# session_8.net
KiCad netlist of a schematic drawn in EAGLE
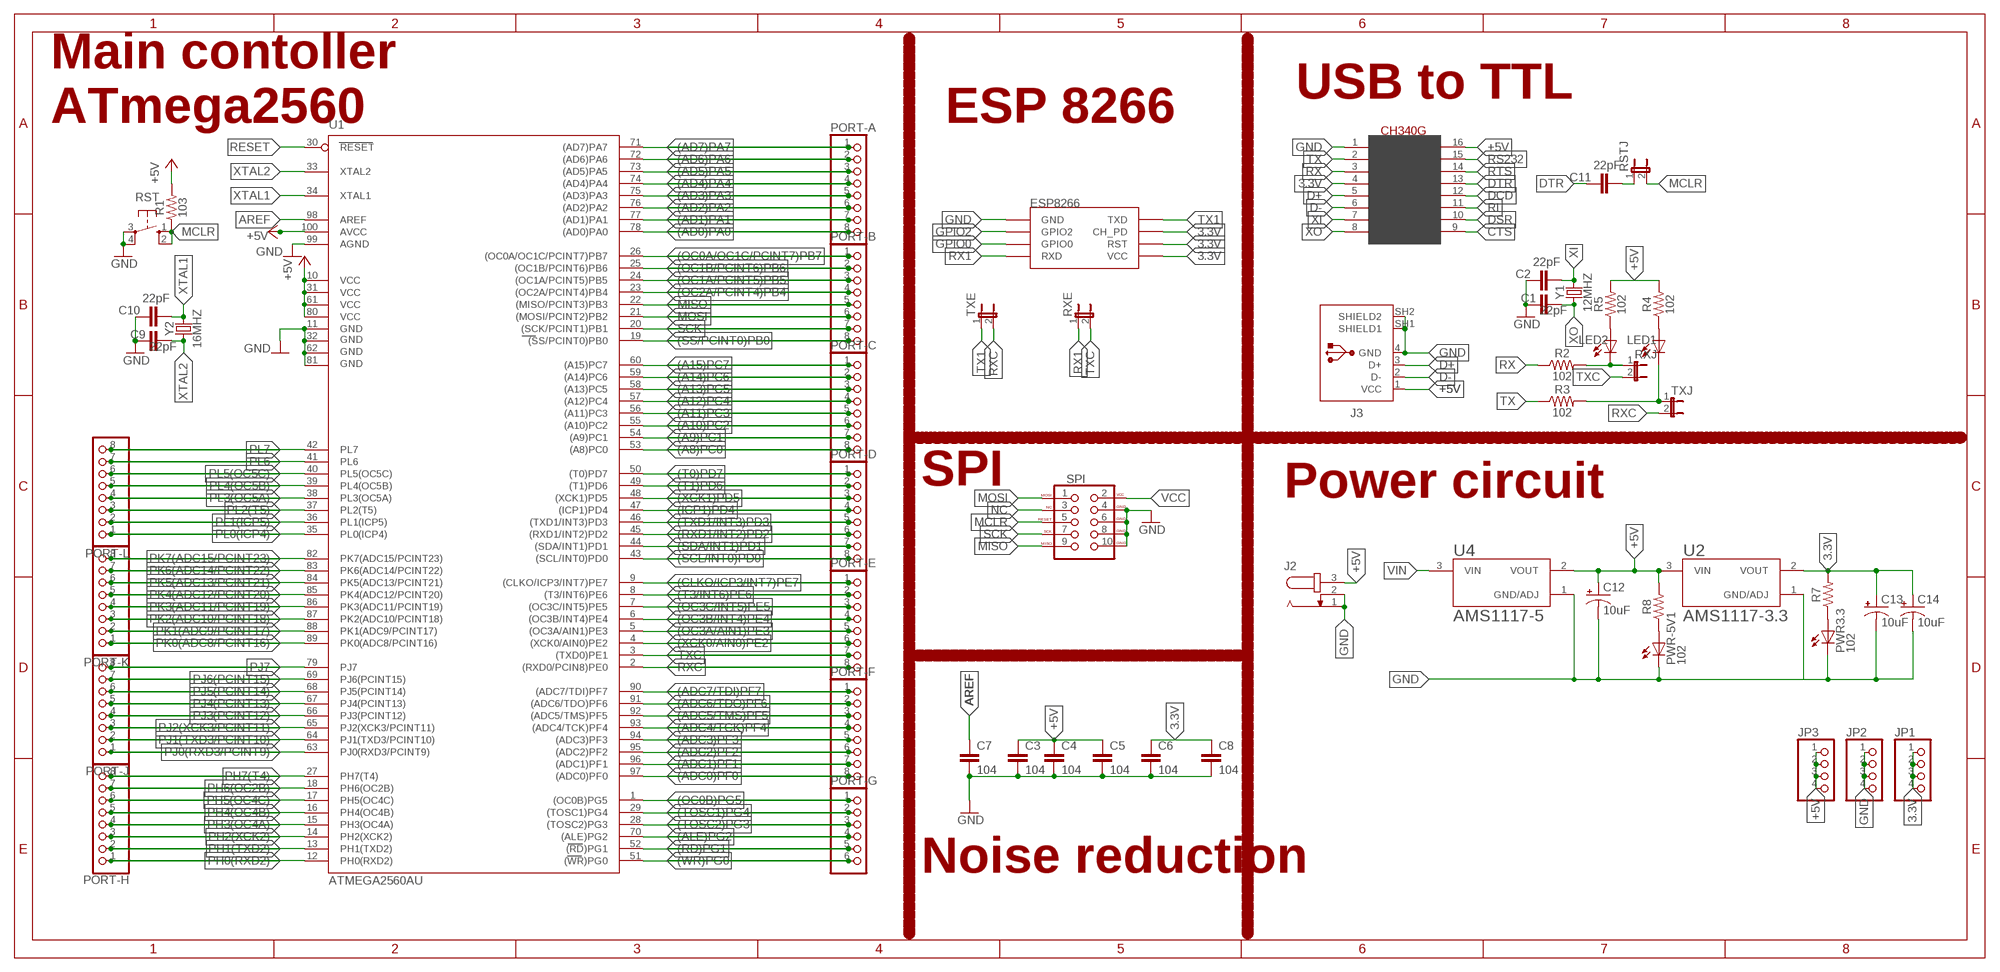
[diagram p0: schematic, sheet 1]

(export (version "E")
  (design (tool "Eeschema 10.0.6"))
  (components
    (comp (ref "C1")
      (value "22pF")
      (footprint "eagle-import:CAP-PTH-2.54")
      (libsource (lib "eagle-import") (part "22PF-PTH-2.54MM-200V-5%"))
    )
    (comp (ref "C2")
      (value "22pF")
      (footprint "eagle-import:CAP-PTH-2.54")
      (libsource (lib "eagle-import") (part "22PF-PTH-2.54MM-200V-5%"))
    )
    (comp (ref "C3")
      (value "104")
      (footprint "eagle-import:CAP-PTH-SMALL-KIT")
      (libsource (lib "eagle-import") (part "0.1UF-KIT-EZ-50V-20%"))
    )
    (comp (ref "C4")
      (value "104")
      (footprint "eagle-import:CAP-PTH-SMALL-KIT")
      (libsource (lib "eagle-import") (part "0.1UF-KIT-EZ-50V-20%"))
    )
    (comp (ref "C5")
      (value "104")
      (footprint "eagle-import:CAP-PTH-SMALL-KIT")
      (libsource (lib "eagle-import") (part "0.1UF-KIT-EZ-50V-20%"))
    )
    (comp (ref "C6")
      (value "104")
      (footprint "eagle-import:CAP-PTH-SMALL-KIT")
      (libsource (lib "eagle-import") (part "0.1UF-KIT-EZ-50V-20%"))
    )
    (comp (ref "C7")
      (value "104")
      (footprint "eagle-import:CAP-PTH-SMALL-KIT")
      (libsource (lib "eagle-import") (part "0.1UF-KIT-EZ-50V-20%"))
    )
    (comp (ref "C8")
      (value "104")
      (footprint "eagle-import:CAP-PTH-SMALL-KIT")
      (libsource (lib "eagle-import") (part "0.1UF-KIT-EZ-50V-20%"))
    )
    (comp (ref "C9")
      (value "22pF")
      (footprint "eagle-import:CAP-PTH-2.54")
      (libsource (lib "eagle-import") (part "22PF-PTH-2.54MM-200V-5%"))
    )
    (comp (ref "C10")
      (value "22pF")
      (footprint "eagle-import:CAP-PTH-2.54")
      (libsource (lib "eagle-import") (part "22PF-PTH-2.54MM-200V-5%"))
    )
    (comp (ref "C11")
      (value "22pF")
      (footprint "eagle-import:CAP-PTH-2.54")
      (libsource (lib "eagle-import") (part "22PF-PTH-2.54MM-200V-5%"))
    )
    (comp (ref "C12")
      (value "10uF")
      (footprint "eagle-import:CPOL-RADIAL-2.5MM-5MM")
      (libsource (lib "eagle-import") (part "10UF-POLAR-RADIAL-2.5MM-25V-20%"))
    )
    (comp (ref "C13")
      (value "10uF")
      (footprint "eagle-import:CPOL-RADIAL-2.5MM-5MM")
      (libsource (lib "eagle-import") (part "10UF-POLAR-RADIAL-2.5MM-25V-20%"))
    )
    (comp (ref "C14")
      (value "10uF")
      (footprint "eagle-import:CPOL-RADIAL-2.5MM-5MM")
      (libsource (lib "eagle-import") (part "10UF-POLAR-RADIAL-2.5MM-25V-20%"))
    )
    (comp (ref "ESP8266")
      (value "ESP01")
      (footprint "eagle-import:ESP01")
      (libsource (lib "eagle-import") (part "ESP01"))
    )
    (comp (ref "J2")
      (value "JACK-PLUG1")
      (footprint "eagle-import:SPC4078")
      (libsource (lib "eagle-import") (part "JACK-PLUG1"))
    )
    (comp (ref "J3")
      (value "61729-1011")
      (footprint "eagle-import:61729-1011BLF")
      (fields (field (name "MANUFACTURER") "Amphenol ICC (FCI)") (field (name "MPN") "61729-1011BLF"))
      (libsource (lib "eagle-import") (part "61729-1011"))
    )
    (comp (ref "JP1")
      (value "PINHD-1X4")
      (footprint "eagle-import:1X04")
      (libsource (lib "eagle-import") (part "PINHD-1X4"))
    )
    (comp (ref "JP2")
      (value "PINHD-1X4")
      (footprint "eagle-import:1X04")
      (libsource (lib "eagle-import") (part "PINHD-1X4"))
    )
    (comp (ref "JP3")
      (value "PINHD-1X4")
      (footprint "eagle-import:1X04")
      (libsource (lib "eagle-import") (part "PINHD-1X4"))
    )
    (comp (ref "LED1")
      (value "LEDCHIP-LED0805")
      (footprint "eagle-import:CHIP-LED0805")
      (libsource (lib "eagle-import") (part "LEDCHIP-LED0805"))
    )
    (comp (ref "LED2")
      (value "LEDCHIP-LED0805")
      (footprint "eagle-import:CHIP-LED0805")
      (libsource (lib "eagle-import") (part "LEDCHIP-LED0805"))
    )
    (comp (ref "PORT-A")
      (value "PINHD-1X8")
      (footprint "eagle-import:1X08")
      (libsource (lib "eagle-import") (part "PINHD-1X8"))
    )
    (comp (ref "PORT-B")
      (value "PINHD-1X8")
      (footprint "eagle-import:1X08")
      (libsource (lib "eagle-import") (part "PINHD-1X8"))
    )
    (comp (ref "PORT-C")
      (value "PINHD-1X8")
      (footprint "eagle-import:1X08")
      (libsource (lib "eagle-import") (part "PINHD-1X8"))
    )
    (comp (ref "PORT-D")
      (value "PINHD-1X8")
      (footprint "eagle-import:1X08")
      (libsource (lib "eagle-import") (part "PINHD-1X8"))
    )
    (comp (ref "PORT-E")
      (value "PINHD-1X8")
      (footprint "eagle-import:1X08")
      (libsource (lib "eagle-import") (part "PINHD-1X8"))
    )
    (comp (ref "PORT-F")
      (value "PINHD-1X8")
      (footprint "eagle-import:1X08")
      (libsource (lib "eagle-import") (part "PINHD-1X8"))
    )
    (comp (ref "PORT-G")
      (value "PINHD-1X6")
      (footprint "eagle-import:1X06")
      (libsource (lib "eagle-import") (part "PINHD-1X6"))
    )
    (comp (ref "PORT-H")
      (value "PINHD-1X8")
      (footprint "eagle-import:1X08")
      (libsource (lib "eagle-import") (part "PINHD-1X8"))
    )
    (comp (ref "PORT-J")
      (value "PINHD-1X8")
      (footprint "eagle-import:1X08")
      (libsource (lib "eagle-import") (part "PINHD-1X8"))
    )
    (comp (ref "PORT-K")
      (value "PINHD-1X8")
      (footprint "eagle-import:1X08")
      (libsource (lib "eagle-import") (part "PINHD-1X8"))
    )
    (comp (ref "PORT-L")
      (value "PINHD-1X8")
      (footprint "eagle-import:1X08")
      (libsource (lib "eagle-import") (part "PINHD-1X8"))
    )
    (comp (ref "PWR-5V1")
      (value "102")
      (footprint "eagle-import:CHIP-LED0805")
      (libsource (lib "eagle-import") (part "LEDCHIP-LED0805"))
    )
    (comp (ref "PWR3.3")
      (value "102")
      (footprint "eagle-import:CHIP-LED0805")
      (libsource (lib "eagle-import") (part "LEDCHIP-LED0805"))
    )
    (comp (ref "R1")
      (value "103")
      (footprint "eagle-import:1206")
      (libsource (lib "eagle-import") (part "RESISTOR1206"))
    )
    (comp (ref "R2")
      (value "102")
      (footprint "eagle-import:1206")
      (libsource (lib "eagle-import") (part "RESISTOR1206"))
    )
    (comp (ref "R3")
      (value "102")
      (footprint "eagle-import:1206")
      (libsource (lib "eagle-import") (part "RESISTOR1206"))
    )
    (comp (ref "R4")
      (value "102")
      (footprint "eagle-import:1206")
      (libsource (lib "eagle-import") (part "RESISTOR1206"))
    )
    (comp (ref "R5")
      (value "102")
      (footprint "eagle-import:1206")
      (libsource (lib "eagle-import") (part "RESISTOR1206"))
    )
    (comp (ref "R7")
      (value "RESISTOR1206")
      (footprint "eagle-import:1206")
      (libsource (lib "eagle-import") (part "RESISTOR1206"))
    )
    (comp (ref "R8")
      (value "RESISTOR1206")
      (footprint "eagle-import:1206")
      (libsource (lib "eagle-import") (part "RESISTOR1206"))
    )
    (comp (ref "RST")
      (value "10-XX")
      (footprint "eagle-import:B3F-10XX")
      (fields (field (name "MPN") "B3F-1000"))
      (libsource (lib "eagle-import") (part "10-XX"))
    )
    (comp (ref "RSTJ")
      (value "JP1E")
      (footprint "eagle-import:JP1")
      (libsource (lib "eagle-import") (part "JP1E"))
    )
    (comp (ref "RXE")
      (value "JP1E")
      (footprint "eagle-import:JP1")
      (libsource (lib "eagle-import") (part "JP1E"))
    )
    (comp (ref "RXJ")
      (value "JP1E")
      (footprint "eagle-import:JP1")
      (libsource (lib "eagle-import") (part "JP1E"))
    )
    (comp (ref "SPI")
      (value "AVR_SPI_PROG_5X2LOCK")
      (footprint "eagle-import:2X5-SHROUDED_LOCK")
      (libsource (lib "eagle-import") (part "AVR_SPI_PROG_5X2LOCK"))
    )
    (comp (ref "TXE")
      (value "JP1E")
      (footprint "eagle-import:JP1")
      (libsource (lib "eagle-import") (part "JP1E"))
    )
    (comp (ref "TXJ")
      (value "JP1E")
      (footprint "eagle-import:JP1")
      (libsource (lib "eagle-import") (part "JP1E"))
    )
    (comp (ref "U$2")
      (value "CH340G")
      (footprint "eagle-import:SOIC16")
      (fields (field (name "MF") "Olimex"))
      (libsource (lib "eagle-import") (part "CH340G"))
    )
    (comp (ref "U1")
      (value "ATMEGA2560AU")
      (footprint "eagle-import:TQFP100")
      (libsource (lib "eagle-import") (part "ATMEGA2560AU"))
    )
    (comp (ref "U2")
      (value "AMS1117-3.3")
      (footprint "eagle-import:SOT229P700X180-4N")
      (fields (field (name "MF") "Advanced Monolithic Systems"))
      (libsource (lib "eagle-import") (part "AMS1117-3.3"))
    )
    (comp (ref "U4")
      (value "AMS1117-5")
      (footprint "eagle-import:SOT229P700X180-4N")
      (fields (field (name "MF") "Advanced Monolithic Systems") (field (name "MP") "AMS1117-3.3"))
      (libsource (lib "eagle-import") (part "AMS1117-3.3"))
    )
    (comp (ref "Y1")
      (value "12MHZ")
      (footprint "eagle-import:HC49U")
      (libsource (lib "eagle-import") (part "CRYSTALPTH-HC49UV"))
    )
    (comp (ref "Y2")
      (value "16MHZ")
      (footprint "eagle-import:HC49U")
      (libsource (lib "eagle-import") (part "CRYSTALPTH-HC49UV"))
    )
  )
  (nets
    (net (code "1") (name "(A8)PC0") (class "Default")
      (node (ref "PORT-C") (pin "8") (pinfunction "8_8") (pintype "passive"))
      (node (ref "U1") (pin "53") (pinfunction "(A8)PC0_53") (pintype "bidirectional"))
    )
    (net (code "2") (name "(A9)PC1") (class "Default")
      (node (ref "PORT-C") (pin "7") (pinfunction "7_7") (pintype "passive"))
      (node (ref "U1") (pin "54") (pinfunction "(A9)PC1_54") (pintype "bidirectional"))
    )
    (net (code "3") (name "(A10)PC2") (class "Default")
      (node (ref "PORT-C") (pin "6") (pinfunction "6_6") (pintype "passive"))
      (node (ref "U1") (pin "55") (pinfunction "(A10)PC2_55") (pintype "bidirectional"))
    )
    (net (code "4") (name "(A11)PC3") (class "Default")
      (node (ref "PORT-C") (pin "5") (pinfunction "5_5") (pintype "passive"))
      (node (ref "U1") (pin "56") (pinfunction "(A11)PC3_56") (pintype "bidirectional"))
    )
    (net (code "5") (name "(A12)PC4") (class "Default")
      (node (ref "PORT-C") (pin "4") (pinfunction "4_4") (pintype "passive"))
      (node (ref "U1") (pin "57") (pinfunction "(A12)PC4_57") (pintype "bidirectional"))
    )
    (net (code "6") (name "(A13)PC5") (class "Default")
      (node (ref "PORT-C") (pin "3") (pinfunction "3_3") (pintype "passive"))
      (node (ref "U1") (pin "58") (pinfunction "(A13)PC5_58") (pintype "bidirectional"))
    )
    (net (code "7") (name "(A14)PC6") (class "Default")
      (node (ref "PORT-C") (pin "2") (pinfunction "2_2") (pintype "passive"))
      (node (ref "U1") (pin "59") (pinfunction "(A14)PC6_59") (pintype "bidirectional"))
    )
    (net (code "8") (name "(A15)PC7") (class "Default")
      (node (ref "PORT-C") (pin "1") (pinfunction "1_1") (pintype "passive"))
      (node (ref "U1") (pin "60") (pinfunction "(A15)PC7_60") (pintype "bidirectional"))
    )
    (net (code "9") (name "(AD0)PA0") (class "Default")
      (node (ref "PORT-A") (pin "8") (pinfunction "8_8") (pintype "passive"))
      (node (ref "U1") (pin "78") (pinfunction "(AD0)PA0_78") (pintype "bidirectional"))
    )
    (net (code "10") (name "(AD1)PA1") (class "Default")
      (node (ref "PORT-A") (pin "7") (pinfunction "7_7") (pintype "passive"))
      (node (ref "U1") (pin "77") (pinfunction "(AD1)PA1_77") (pintype "bidirectional"))
    )
    (net (code "11") (name "(AD2)PA2") (class "Default")
      (node (ref "PORT-A") (pin "6") (pinfunction "6_6") (pintype "passive"))
      (node (ref "U1") (pin "76") (pinfunction "(AD2)PA2_76") (pintype "bidirectional"))
    )
    (net (code "12") (name "(AD3)PA3") (class "Default")
      (node (ref "PORT-A") (pin "5") (pinfunction "5_5") (pintype "passive"))
      (node (ref "U1") (pin "75") (pinfunction "(AD3)PA3_75") (pintype "bidirectional"))
    )
    (net (code "13") (name "(AD4)PA4") (class "Default")
      (node (ref "PORT-A") (pin "4") (pinfunction "4_4") (pintype "passive"))
      (node (ref "U1") (pin "74") (pinfunction "(AD4)PA4_74") (pintype "bidirectional"))
    )
    (net (code "14") (name "(AD5)PA5") (class "Default")
      (node (ref "PORT-A") (pin "3") (pinfunction "3_3") (pintype "passive"))
      (node (ref "U1") (pin "73") (pinfunction "(AD5)PA5_73") (pintype "bidirectional"))
    )
    (net (code "15") (name "(AD6)PA6") (class "Default")
      (node (ref "PORT-A") (pin "2") (pinfunction "2_2") (pintype "passive"))
      (node (ref "U1") (pin "72") (pinfunction "(AD6)PA6_72") (pintype "bidirectional"))
    )
    (net (code "16") (name "(AD7)PA7") (class "Default")
      (node (ref "PORT-A") (pin "1") (pinfunction "1_1") (pintype "passive"))
      (node (ref "U1") (pin "71") (pinfunction "(AD7)PA7_71") (pintype "bidirectional"))
    )
    (net (code "17") (name "(ADC0)PF0") (class "Default")
      (node (ref "PORT-F") (pin "8") (pinfunction "8_8") (pintype "passive"))
      (node (ref "U1") (pin "97") (pinfunction "(ADC0)PF0_97") (pintype "bidirectional"))
    )
    (net (code "18") (name "(ADC1)PF1") (class "Default")
      (node (ref "PORT-F") (pin "7") (pinfunction "7_7") (pintype "passive"))
      (node (ref "U1") (pin "96") (pinfunction "(ADC1)PF1_96") (pintype "bidirectional"))
    )
    (net (code "19") (name "(ADC2)PF2") (class "Default")
      (node (ref "PORT-F") (pin "6") (pinfunction "6_6") (pintype "passive"))
      (node (ref "U1") (pin "95") (pinfunction "(ADC2)PF2_95") (pintype "bidirectional"))
    )
    (net (code "20") (name "(ADC3)PF3") (class "Default")
      (node (ref "PORT-F") (pin "5") (pinfunction "5_5") (pintype "passive"))
      (node (ref "U1") (pin "94") (pinfunction "(ADC3)PF3_94") (pintype "bidirectional"))
    )
    (net (code "21") (name "(ADC4{slash}TCK)PF4") (class "Default")
      (node (ref "PORT-F") (pin "4") (pinfunction "4_4") (pintype "passive"))
      (node (ref "U1") (pin "93") (pinfunction "(ADC4/TCK)PF4_93") (pintype "bidirectional"))
    )
    (net (code "22") (name "(ADC5{slash}TMS)PF5") (class "Default")
      (node (ref "PORT-F") (pin "3") (pinfunction "3_3") (pintype "passive"))
      (node (ref "U1") (pin "92") (pinfunction "(ADC5/TMS)PF5_92") (pintype "bidirectional"))
    )
    (net (code "23") (name "(ADC6{slash}TDO)PF6") (class "Default")
      (node (ref "PORT-F") (pin "2") (pinfunction "2_2") (pintype "passive"))
      (node (ref "U1") (pin "91") (pinfunction "(ADC6/TDO)PF6_91") (pintype "bidirectional"))
    )
    (net (code "24") (name "(ADC7{slash}TDI)PF7") (class "Default")
      (node (ref "PORT-F") (pin "1") (pinfunction "1_1") (pintype "passive"))
      (node (ref "U1") (pin "90") (pinfunction "(ADC7/TDI)PF7_90") (pintype "bidirectional"))
    )
    (net (code "25") (name "(ALE)PG2") (class "Default")
      (node (ref "PORT-G") (pin "4") (pinfunction "4_4") (pintype "passive"))
      (node (ref "U1") (pin "70") (pinfunction "(ALE)PG2_70") (pintype "bidirectional"))
    )
    (net (code "26") (name "(CLKO{slash}ICP3{slash}INT7)PE7") (class "Default")
      (node (ref "PORT-E") (pin "1") (pinfunction "1_1") (pintype "passive"))
      (node (ref "U1") (pin "9") (pinfunction "(CLKO/ICP3/INT7)PE7_9") (pintype "bidirectional"))
    )
    (net (code "27") (name "(ICP1)PD4") (class "Default")
      (node (ref "PORT-D") (pin "4") (pinfunction "4_4") (pintype "passive"))
      (node (ref "U1") (pin "47") (pinfunction "(ICP1)PD4_47") (pintype "bidirectional"))
    )
    (net (code "28") (name "(OC0A{slash}OC1C{slash}PCINT7)PB7") (class "Default")
      (node (ref "PORT-B") (pin "1") (pinfunction "1_1") (pintype "passive"))
      (node (ref "U1") (pin "26") (pinfunction "(OC0A/OC1C/PCINT7)PB7_26") (pintype "bidirectional"))
    )
    (net (code "29") (name "(OC0B)PG5") (class "Default")
      (node (ref "PORT-G") (pin "1") (pinfunction "1_1") (pintype "passive"))
      (node (ref "U1") (pin "1") (pinfunction "(OC0B)PG5_1") (pintype "bidirectional"))
    )
    (net (code "30") (name "(OC1A{slash}PCINT5)PB5") (class "Default")
      (node (ref "PORT-B") (pin "3") (pinfunction "3_3") (pintype "passive"))
      (node (ref "U1") (pin "24") (pinfunction "(OC1A/PCINT5)PB5_24") (pintype "bidirectional"))
    )
    (net (code "31") (name "(OC1B{slash}PCINT6)PB6") (class "Default")
      (node (ref "PORT-B") (pin "2") (pinfunction "2_2") (pintype "passive"))
      (node (ref "U1") (pin "25") (pinfunction "(OC1B/PCINT6)PB6_25") (pintype "bidirectional"))
    )
    (net (code "32") (name "(OC2A{slash}PCINT4)PB4") (class "Default")
      (node (ref "PORT-B") (pin "4") (pinfunction "4_4") (pintype "passive"))
      (node (ref "U1") (pin "23") (pinfunction "(OC2A/PCINT4)PB4_23") (pintype "bidirectional"))
    )
    (net (code "33") (name "(OC3A{slash}AIN1)PE3") (class "Default")
      (node (ref "PORT-E") (pin "5") (pinfunction "5_5") (pintype "passive"))
      (node (ref "U1") (pin "5") (pinfunction "(OC3A/AIN1)PE3_5") (pintype "bidirectional"))
    )
    (net (code "34") (name "(OC3B{slash}INT4)PE4") (class "Default")
      (node (ref "PORT-E") (pin "4") (pinfunction "4_4") (pintype "passive"))
      (node (ref "U1") (pin "6") (pinfunction "(OC3B/INT4)PE4_6") (pintype "bidirectional"))
    )
    (net (code "35") (name "(OC3C{slash}INT5)PE5") (class "Default")
      (node (ref "PORT-E") (pin "3") (pinfunction "3_3") (pintype "passive"))
      (node (ref "U1") (pin "7") (pinfunction "(OC3C/INT5)PE5_7") (pintype "bidirectional"))
    )
    (net (code "36") (name "(RD)PG1") (class "Default")
      (node (ref "PORT-G") (pin "5") (pinfunction "5_5") (pintype "passive"))
      (node (ref "U1") (pin "52") (pinfunction "(RD)PG1_52") (pintype "bidirectional"))
    )
    (net (code "37") (name "(RXD1{slash}INT2)PD2") (class "Default")
      (node (ref "PORT-D") (pin "6") (pinfunction "6_6") (pintype "passive"))
      (node (ref "U1") (pin "45") (pinfunction "(RXD1/INT2)PD2_45") (pintype "bidirectional"))
    )
    (net (code "38") (name "(SCL{slash}INT0)PD0") (class "Default")
      (node (ref "PORT-D") (pin "8") (pinfunction "8_8") (pintype "passive"))
      (node (ref "U1") (pin "43") (pinfunction "(SCL/INT0)PD0_43") (pintype "bidirectional"))
    )
    (net (code "39") (name "(SDA{slash}INT1)PD1") (class "Default")
      (node (ref "PORT-D") (pin "7") (pinfunction "7_7") (pintype "passive"))
      (node (ref "U1") (pin "44") (pinfunction "(SDA/INT1)PD1_44") (pintype "bidirectional"))
    )
    (net (code "40") (name "(SS{slash}PCINT0)PB0") (class "Default")
      (node (ref "PORT-B") (pin "8") (pinfunction "8_8") (pintype "passive"))
      (node (ref "U1") (pin "19") (pinfunction "(SS/PCINT0)PB0_19") (pintype "bidirectional"))
    )
    (net (code "41") (name "(T0)PD7") (class "Default")
      (node (ref "PORT-D") (pin "1") (pinfunction "1_1") (pintype "passive"))
      (node (ref "U1") (pin "50") (pinfunction "(T0)PD7_50") (pintype "bidirectional"))
    )
    (net (code "42") (name "(T1)PD6") (class "Default")
      (node (ref "PORT-D") (pin "2") (pinfunction "2_2") (pintype "passive"))
      (node (ref "U1") (pin "49") (pinfunction "(T1)PD6_49") (pintype "bidirectional"))
    )
    (net (code "43") (name "(T3{slash}INT6)PE6") (class "Default")
      (node (ref "PORT-E") (pin "2") (pinfunction "2_2") (pintype "passive"))
      (node (ref "U1") (pin "8") (pinfunction "(T3/INT6)PE6_8") (pintype "bidirectional"))
    )
    (net (code "44") (name "(TOSC1)PG4") (class "Default")
      (node (ref "PORT-G") (pin "2") (pinfunction "2_2") (pintype "passive"))
      (node (ref "U1") (pin "29") (pinfunction "(TOSC1)PG4_29") (pintype "bidirectional"))
    )
    (net (code "45") (name "(TOSC2)PG3") (class "Default")
      (node (ref "PORT-G") (pin "3") (pinfunction "3_3") (pintype "passive"))
      (node (ref "U1") (pin "28") (pinfunction "(TOSC2)PG3_28") (pintype "bidirectional"))
    )
    (net (code "46") (name "(TXD1{slash}INT3)PD3") (class "Default")
      (node (ref "PORT-D") (pin "5") (pinfunction "5_5") (pintype "passive"))
      (node (ref "U1") (pin "46") (pinfunction "(TXD1/INT3)PD3_46") (pintype "bidirectional"))
    )
    (net (code "47") (name "(WR)PG0") (class "Default")
      (node (ref "PORT-G") (pin "6") (pinfunction "6_6") (pintype "passive"))
      (node (ref "U1") (pin "51") (pinfunction "(WR)PG0_51") (pintype "bidirectional"))
    )
    (net (code "48") (name "(XCK0{slash}AIN0)PE2") (class "Default")
      (node (ref "PORT-E") (pin "6") (pinfunction "6_6") (pintype "passive"))
      (node (ref "U1") (pin "4") (pinfunction "(XCK0/AIN0)PE2_4") (pintype "bidirectional"))
    )
    (net (code "49") (name "(XCK1)PD5") (class "Default")
      (node (ref "PORT-D") (pin "3") (pinfunction "3_3") (pintype "passive"))
      (node (ref "U1") (pin "48") (pinfunction "(XCK1)PD5_48") (pintype "bidirectional"))
    )
    (net (code "50") (name "+5V") (class "Default")
      (node (ref "C12") (pin "1") (pinfunction "+_1") (pintype "passive"))
      (node (ref "C3") (pin "1") (pinfunction "1_1") (pintype "passive"))
      (node (ref "C4") (pin "1") (pinfunction "1_1") (pintype "passive"))
      (node (ref "C5") (pin "1") (pinfunction "1_1") (pintype "passive"))
      (node (ref "J2") (pin "3") (pinfunction "3_3") (pintype "passive"))
      (node (ref "J3") (pin "1") (pinfunction "VCC_1") (pintype "power_in"))
      (node (ref "JP3") (pin "1") (pinfunction "1_1") (pintype "passive"))
      (node (ref "JP3") (pin "2") (pinfunction "2_2") (pintype "passive"))
      (node (ref "JP3") (pin "3") (pinfunction "3_3") (pintype "passive"))
      (node (ref "JP3") (pin "4") (pinfunction "4_4") (pintype "passive"))
      (node (ref "R1") (pin "2") (pinfunction "2_2") (pintype "passive"))
      (node (ref "R4") (pin "2") (pinfunction "2_2") (pintype "passive"))
      (node (ref "R5") (pin "2") (pinfunction "2_2") (pintype "passive"))
      (node (ref "R8") (pin "2") (pinfunction "2_2") (pintype "passive"))
      (node (ref "U$2") (pin "16") (pinfunction "VCC_16") (pintype "bidirectional"))
      (node (ref "U1") (pin "10") (pinfunction "VCC_10") (pintype "power_in"))
      (node (ref "U1") (pin "100") (pinfunction "AVCC_100") (pintype "power_in"))
      (node (ref "U1") (pin "31") (pinfunction "VCC1_31") (pintype "power_in"))
      (node (ref "U1") (pin "61") (pinfunction "VCC2_61") (pintype "power_in"))
      (node (ref "U1") (pin "80") (pinfunction "VCC3_80") (pintype "power_in"))
      (node (ref "U2") (pin "3") (pinfunction "VIN_3") (pintype "input"))
      (node (ref "U4") (pin "2") (pinfunction "VOUT_2") (pintype "output"))
    )
    (net (code "51") (name "3.3V") (class "Default")
      (node (ref "C13") (pin "1") (pinfunction "+_1") (pintype "passive"))
      (node (ref "C14") (pin "1") (pinfunction "+_1") (pintype "passive"))
      (node (ref "C6") (pin "1") (pinfunction "1_1") (pintype "passive"))
      (node (ref "C8") (pin "1") (pinfunction "1_1") (pintype "passive"))
      (node (ref "ESP8266") (pin "CH_PD") (pinfunction "CH_PD_CH_PD") (pintype "bidirectional"))
      (node (ref "ESP8266") (pin "RST") (pinfunction "RST_RST") (pintype "bidirectional"))
      (node (ref "ESP8266") (pin "VCC") (pinfunction "VCC_VCC") (pintype "bidirectional"))
      (node (ref "JP1") (pin "1") (pinfunction "1_1") (pintype "passive"))
      (node (ref "JP1") (pin "2") (pinfunction "2_2") (pintype "passive"))
      (node (ref "JP1") (pin "3") (pinfunction "3_3") (pintype "passive"))
      (node (ref "JP1") (pin "4") (pinfunction "4_4") (pintype "passive"))
      (node (ref "R7") (pin "2") (pinfunction "2_2") (pintype "passive"))
      (node (ref "U$2") (pin "4") (pinfunction "V3_4") (pintype "bidirectional"))
      (node (ref "U2") (pin "2") (pinfunction "VOUT_2") (pintype "output"))
    )
    (net (code "52") (name "AREF") (class "Default")
      (node (ref "C7") (pin "1") (pinfunction "1_1") (pintype "passive"))
      (node (ref "U1") (pin "98") (pinfunction "AREF_98") (pintype "bidirectional"))
    )
    (net (code "53") (name "CTS") (class "Default")
      (node (ref "U$2") (pin "9") (pinfunction "CTS_9") (pintype "bidirectional"))
    )
    (net (code "54") (name "D+") (class "Default")
      (node (ref "J3") (pin "3") (pinfunction "D+_3") (pintype "bidirectional"))
      (node (ref "U$2") (pin "5") (pinfunction "D+_5") (pintype "bidirectional"))
    )
    (net (code "55") (name "D-") (class "Default")
      (node (ref "J3") (pin "2") (pinfunction "D-_2") (pintype "bidirectional"))
      (node (ref "U$2") (pin "6") (pinfunction "D-_6") (pintype "bidirectional"))
    )
    (net (code "56") (name "DCD") (class "Default")
      (node (ref "U$2") (pin "12") (pinfunction "DCD_12") (pintype "bidirectional"))
    )
    (net (code "57") (name "DSR") (class "Default")
      (node (ref "U$2") (pin "10") (pinfunction "DSR_10") (pintype "bidirectional"))
    )
    (net (code "58") (name "DTR") (class "Default")
      (node (ref "C11") (pin "1") (pinfunction "1_1") (pintype "passive"))
      (node (ref "U$2") (pin "13") (pinfunction "DTR_13") (pintype "bidirectional"))
    )
    (net (code "59") (name "GND") (class "Default")
      (node (ref "C1") (pin "1") (pinfunction "1_1") (pintype "passive"))
      (node (ref "C10") (pin "1") (pinfunction "1_1") (pintype "passive"))
      (node (ref "C12") (pin "2") (pinfunction "-_2") (pintype "passive"))
      (node (ref "C13") (pin "2") (pinfunction "-_2") (pintype "passive"))
      (node (ref "C14") (pin "2") (pinfunction "-_2") (pintype "passive"))
      (node (ref "C2") (pin "1") (pinfunction "1_1") (pintype "passive"))
      (node (ref "C3") (pin "2") (pinfunction "2_2") (pintype "passive"))
      (node (ref "C4") (pin "2") (pinfunction "2_2") (pintype "passive"))
      (node (ref "C5") (pin "2") (pinfunction "2_2") (pintype "passive"))
      (node (ref "C6") (pin "2") (pinfunction "2_2") (pintype "passive"))
      (node (ref "C7") (pin "2") (pinfunction "2_2") (pintype "passive"))
      (node (ref "C8") (pin "2") (pinfunction "2_2") (pintype "passive"))
      (node (ref "C9") (pin "1") (pinfunction "1_1") (pintype "passive"))
      (node (ref "ESP8266") (pin "GND") (pinfunction "GND_GND") (pintype "bidirectional"))
      (node (ref "J2") (pin "1") (pinfunction "1_1") (pintype "passive"))
      (node (ref "J2") (pin "2") (pinfunction "2_2") (pintype "passive"))
      (node (ref "J3") (pin "4") (pinfunction "GND_4") (pintype "power_in"))
      (node (ref "J3") (pin "SH1") (pinfunction "SHIELD1_SH1") (pintype "power_in"))
      (node (ref "J3") (pin "SH2") (pinfunction "SHIELD2_SH2") (pintype "power_in"))
      (node (ref "JP2") (pin "1") (pinfunction "1_1") (pintype "passive"))
      (node (ref "JP2") (pin "2") (pinfunction "2_2") (pintype "passive"))
      (node (ref "JP2") (pin "3") (pinfunction "3_3") (pintype "passive"))
      (node (ref "JP2") (pin "4") (pinfunction "4_4") (pintype "passive"))
      (node (ref "PWR-5V1") (pin "C") (pinfunction "C_C") (pintype "passive"))
      (node (ref "PWR3.3") (pin "C") (pinfunction "C_C") (pintype "passive"))
      (node (ref "RST") (pin "3") (pinfunction "P_3") (pintype "passive"))
      (node (ref "RST") (pin "4") (pinfunction "P1_4") (pintype "passive"))
      (node (ref "SPI") (pin "10") (pinfunction "GND_10") (pintype "power_in"))
      (node (ref "SPI") (pin "4") (pinfunction "GND_4") (pintype "power_in"))
      (node (ref "SPI") (pin "6") (pinfunction "GND_6") (pintype "power_in"))
      (node (ref "SPI") (pin "8") (pinfunction "GND_8") (pintype "power_in"))
      (node (ref "U$2") (pin "1") (pinfunction "GND_1") (pintype "bidirectional"))
      (node (ref "U1") (pin "11") (pinfunction "GND_11") (pintype "power_in"))
      (node (ref "U1") (pin "32") (pinfunction "GND1_32") (pintype "power_in"))
      (node (ref "U1") (pin "62") (pinfunction "GND2_62") (pintype "power_in"))
      (node (ref "U1") (pin "81") (pinfunction "GND3_81") (pintype "power_in"))
      (node (ref "U1") (pin "99") (pinfunction "AGND_99") (pintype "power_in"))
      (node (ref "U2") (pin "1") (pinfunction "GND/ADJ_1") (pintype "power_in"))
      (node (ref "U4") (pin "1") (pinfunction "GND/ADJ_1") (pintype "power_in"))
    )
    (net (code "60") (name "GPIO0") (class "Default")
      (node (ref "ESP8266") (pin "GPIO0") (pinfunction "GPIO0_GPIO0") (pintype "bidirectional"))
    )
    (net (code "61") (name "GPIO2") (class "Default")
      (node (ref "ESP8266") (pin "GPIO2") (pinfunction "GPIO2_GPIO2") (pintype "bidirectional"))
    )
    (net (code "62") (name "MCLR") (class "Default")
      (node (ref "R1") (pin "1") (pinfunction "1_1") (pintype "passive"))
      (node (ref "RST") (pin "1") (pinfunction "S_1") (pintype "passive"))
      (node (ref "RST") (pin "2") (pinfunction "S1_2") (pintype "passive"))
      (node (ref "RSTJ") (pin "2") (pinfunction "2_2") (pintype "passive"))
      (node (ref "SPI") (pin "5") (pinfunction "RESET_5") (pintype "passive"))
    )
    (net (code "63") (name "MISO") (class "Default")
      (node (ref "PORT-B") (pin "5") (pinfunction "5_5") (pintype "passive"))
      (node (ref "SPI") (pin "9") (pinfunction "MISO_9") (pintype "passive"))
      (node (ref "U1") (pin "22") (pinfunction "(MISO/PCINT3)PB3_22") (pintype "bidirectional"))
    )
    (net (code "64") (name "MOSI") (class "Default")
      (node (ref "PORT-B") (pin "6") (pinfunction "6_6") (pintype "passive"))
      (node (ref "SPI") (pin "1") (pinfunction "MOSI_1") (pintype "passive"))
      (node (ref "U1") (pin "21") (pinfunction "(MOSI/PCINT2)PB2_21") (pintype "bidirectional"))
    )
    (net (code "66") (name "NC") (class "Default")
      (node (ref "SPI") (pin "3") (pinfunction "NC_3") (pintype "no_connect"))
    )
    (net (code "67") (name "Net-(C11-Pad2)") (class "Default")
      (node (ref "C11") (pin "2") (pinfunction "2_2") (pintype "passive"))
      (node (ref "RSTJ") (pin "1") (pinfunction "1_1") (pintype "passive"))
    )
    (net (code "68") (name "Net-(LED1-PadA)") (class "Default")
      (node (ref "LED1") (pin "A") (pinfunction "A_A") (pintype "passive"))
      (node (ref "R4") (pin "1") (pinfunction "1_1") (pintype "passive"))
    )
    (net (code "69") (name "Net-(LED1-PadC)") (class "Default")
      (node (ref "LED1") (pin "C") (pinfunction "C_C") (pintype "passive"))
      (node (ref "R3") (pin "2") (pinfunction "2_2") (pintype "passive"))
      (node (ref "TXJ") (pin "1") (pinfunction "1_1") (pintype "passive"))
    )
    (net (code "70") (name "Net-(LED2-PadA)") (class "Default")
      (node (ref "LED2") (pin "A") (pinfunction "A_A") (pintype "passive"))
      (node (ref "R5") (pin "1") (pinfunction "1_1") (pintype "passive"))
    )
    (net (code "71") (name "Net-(LED2-PadC)") (class "Default")
      (node (ref "LED2") (pin "C") (pinfunction "C_C") (pintype "passive"))
      (node (ref "R2") (pin "2") (pinfunction "2_2") (pintype "passive"))
      (node (ref "RXJ") (pin "1") (pinfunction "1_1") (pintype "passive"))
    )
    (net (code "72") (name "Net-(PWR-5V1-PadA)") (class "Default")
      (node (ref "PWR-5V1") (pin "A") (pinfunction "A_A") (pintype "passive"))
      (node (ref "R8") (pin "1") (pinfunction "1_1") (pintype "passive"))
    )
    (net (code "73") (name "Net-(PWR3.3-PadA)") (class "Default")
      (node (ref "PWR3.3") (pin "A") (pinfunction "A_A") (pintype "passive"))
      (node (ref "R7") (pin "1") (pinfunction "1_1") (pintype "passive"))
    )
    (net (code "74") (name "PH0(RXD2)") (class "Default")
      (node (ref "PORT-H") (pin "1") (pinfunction "1_1") (pintype "passive"))
      (node (ref "U1") (pin "12") (pinfunction "PH0(RXD2)_12") (pintype "bidirectional"))
    )
    (net (code "75") (name "PH1(TXD2)") (class "Default")
      (node (ref "PORT-H") (pin "2") (pinfunction "2_2") (pintype "passive"))
      (node (ref "U1") (pin "13") (pinfunction "PH1(TXD2)_13") (pintype "bidirectional"))
    )
    (net (code "76") (name "PH2(XCK2)") (class "Default")
      (node (ref "PORT-H") (pin "3") (pinfunction "3_3") (pintype "passive"))
      (node (ref "U1") (pin "14") (pinfunction "PH2(XCK2)_14") (pintype "bidirectional"))
    )
    (net (code "77") (name "PH3(OC4A)") (class "Default")
      (node (ref "PORT-H") (pin "4") (pinfunction "4_4") (pintype "passive"))
      (node (ref "U1") (pin "15") (pinfunction "PH3(OC4A)_15") (pintype "bidirectional"))
    )
    (net (code "78") (name "PH4(OC4B)") (class "Default")
      (node (ref "PORT-H") (pin "5") (pinfunction "5_5") (pintype "passive"))
      (node (ref "U1") (pin "16") (pinfunction "PH4(OC4B)_16") (pintype "bidirectional"))
    )
    (net (code "79") (name "PH5(OC4C)") (class "Default")
      (node (ref "PORT-H") (pin "6") (pinfunction "6_6") (pintype "passive"))
      (node (ref "U1") (pin "17") (pinfunction "PH5(OC4C)_17") (pintype "bidirectional"))
    )
    (net (code "80") (name "PH6(OC2B)") (class "Default")
      (node (ref "PORT-H") (pin "7") (pinfunction "7_7") (pintype "passive"))
      (node (ref "U1") (pin "18") (pinfunction "PH6(OC2B)_18") (pintype "bidirectional"))
    )
    (net (code "81") (name "PH7(T4)") (class "Default")
      (node (ref "PORT-H") (pin "8") (pinfunction "8_8") (pintype "passive"))
      (node (ref "U1") (pin "27") (pinfunction "PH7(T4)_27") (pintype "bidirectional"))
    )
    (net (code "82") (name "PJ0(RXD3{slash}PCINT9)") (class "Default")
      (node (ref "PORT-J") (pin "1") (pinfunction "1_1") (pintype "passive"))
      (node (ref "U1") (pin "63") (pinfunction "PJ0(RXD3/PCINT9)_63") (pintype "bidirectional"))
    )
    (net (code "83") (name "PJ1(TXD3{slash}PCINT10)") (class "Default")
      (node (ref "PORT-J") (pin "2") (pinfunction "2_2") (pintype "passive"))
      (node (ref "U1") (pin "64") (pinfunction "PJ1(TXD3/PCINT10)_64") (pintype "bidirectional"))
    )
    (net (code "84") (name "PJ2(XCK3{slash}PCINT11)") (class "Default")
      (node (ref "PORT-J") (pin "3") (pinfunction "3_3") (pintype "passive"))
      (node (ref "U1") (pin "65") (pinfunction "PJ2(XCK3/PCINT11)_65") (pintype "bidirectional"))
    )
    (net (code "85") (name "PJ3(PCINT12)") (class "Default")
      (node (ref "PORT-J") (pin "4") (pinfunction "4_4") (pintype "passive"))
      (node (ref "U1") (pin "66") (pinfunction "PJ3(PCINT12)_66") (pintype "bidirectional"))
    )
    (net (code "86") (name "PJ4(PCINT13)") (class "Default")
      (node (ref "PORT-J") (pin "5") (pinfunction "5_5") (pintype "passive"))
      (node (ref "U1") (pin "67") (pinfunction "PJ4(PCINT13)_67") (pintype "bidirectional"))
    )
    (net (code "87") (name "PJ5(PCINT14)") (class "Default")
      (node (ref "PORT-J") (pin "6") (pinfunction "6_6") (pintype "passive"))
      (node (ref "U1") (pin "68") (pinfunction "PJ5(PCINT14)_68") (pintype "bidirectional"))
    )
    (net (code "88") (name "PJ6(PCINT15)") (class "Default")
      (node (ref "PORT-J") (pin "7") (pinfunction "7_7") (pintype "passive"))
      (node (ref "U1") (pin "69") (pinfunction "PJ6(PCINT15)_69") (pintype "bidirectional"))
    )
    (net (code "89") (name "PJ7") (class "Default")
      (node (ref "PORT-J") (pin "8") (pinfunction "8_8") (pintype "passive"))
      (node (ref "U1") (pin "79") (pinfunction "PJ7_79") (pintype "bidirectional"))
    )
    (net (code "90") (name "PK0(ADC8{slash}PCINT16)") (class "Default")
      (node (ref "PORT-K") (pin "1") (pinfunction "1_1") (pintype "passive"))
      (node (ref "U1") (pin "89") (pinfunction "PK0(ADC8/PCINT16)_89") (pintype "bidirectional"))
    )
    (net (code "91") (name "PK1(ADC9{slash}PCINT17)") (class "Default")
      (node (ref "PORT-K") (pin "2") (pinfunction "2_2") (pintype "passive"))
      (node (ref "U1") (pin "88") (pinfunction "PK1(ADC9/PCINT17)_88") (pintype "bidirectional"))
    )
    (net (code "92") (name "PK2(ADC10{slash}PCINT18)") (class "Default")
      (node (ref "PORT-K") (pin "3") (pinfunction "3_3") (pintype "passive"))
      (node (ref "U1") (pin "87") (pinfunction "PK2(ADC10/PCINT18)_87") (pintype "bidirectional"))
    )
    (net (code "93") (name "PK3(ADC11{slash}PCINT19)") (class "Default")
      (node (ref "PORT-K") (pin "4") (pinfunction "4_4") (pintype "passive"))
      (node (ref "U1") (pin "86") (pinfunction "PK3(ADC11/PCINT19)_86") (pintype "bidirectional"))
    )
    (net (code "94") (name "PK4(ADC12{slash}PCINT20)") (class "Default")
      (node (ref "PORT-K") (pin "5") (pinfunction "5_5") (pintype "passive"))
      (node (ref "U1") (pin "85") (pinfunction "PK4(ADC12/PCINT20)_85") (pintype "bidirectional"))
    )
    (net (code "95") (name "PK5(ADC13{slash}PCINT21)") (class "Default")
      (node (ref "PORT-K") (pin "6") (pinfunction "6_6") (pintype "passive"))
      (node (ref "U1") (pin "84") (pinfunction "PK5(ADC13/PCINT21)_84") (pintype "bidirectional"))
    )
    (net (code "96") (name "PK6(ADC14{slash}PCINT22)") (class "Default")
      (node (ref "PORT-K") (pin "7") (pinfunction "7_7") (pintype "passive"))
      (node (ref "U1") (pin "83") (pinfunction "PK6(ADC14/PCINT22)_83") (pintype "bidirectional"))
    )
    (net (code "97") (name "PK7(ADC15{slash}PCINT23)") (class "Default")
      (node (ref "PORT-K") (pin "8") (pinfunction "8_8") (pintype "passive"))
      (node (ref "U1") (pin "82") (pinfunction "PK7(ADC15/PCINT23)_82") (pintype "bidirectional"))
    )
    (net (code "98") (name "PL0(ICP4)") (class "Default")
      (node (ref "PORT-L") (pin "1") (pinfunction "1_1") (pintype "passive"))
      (node (ref "U1") (pin "35") (pinfunction "PL0(ICP4)_35") (pintype "bidirectional"))
    )
    (net (code "99") (name "PL1(ICP5)") (class "Default")
      (node (ref "PORT-L") (pin "2") (pinfunction "2_2") (pintype "passive"))
      (node (ref "U1") (pin "36") (pinfunction "PL1(ICP5)_36") (pintype "bidirectional"))
    )
    (net (code "100") (name "PL2(T5)") (class "Default")
      (node (ref "PORT-L") (pin "3") (pinfunction "3_3") (pintype "passive"))
      (node (ref "U1") (pin "37") (pinfunction "PL2(T5)_37") (pintype "bidirectional"))
    )
    (net (code "101") (name "PL3(OC5A)") (class "Default")
      (node (ref "PORT-L") (pin "4") (pinfunction "4_4") (pintype "passive"))
      (node (ref "U1") (pin "38") (pinfunction "PL3(OC5A)_38") (pintype "bidirectional"))
    )
    (net (code "102") (name "PL4(OC5B)") (class "Default")
      (node (ref "PORT-L") (pin "5") (pinfunction "5_5") (pintype "passive"))
      (node (ref "U1") (pin "39") (pinfunction "PL4(OC5B)_39") (pintype "bidirectional"))
    )
    (net (code "103") (name "PL5(OC5C)") (class "Default")
      (node (ref "PORT-L") (pin "6") (pinfunction "6_6") (pintype "passive"))
      (node (ref "U1") (pin "40") (pinfunction "PL5(OC5C)_40") (pintype "bidirectional"))
    )
    (net (code "104") (name "PL6") (class "Default")
      (node (ref "PORT-L") (pin "7") (pinfunction "7_7") (pintype "passive"))
      (node (ref "U1") (pin "41") (pinfunction "PL6_41") (pintype "bidirectional"))
    )
    (net (code "105") (name "PL7") (class "Default")
      (node (ref "PORT-L") (pin "8") (pinfunction "8_8") (pintype "passive"))
      (node (ref "U1") (pin "42") (pinfunction "PL7_42") (pintype "bidirectional"))
    )
    (net (code "106") (name "RESET") (class "Default")
      (node (ref "U1") (pin "30") (pinfunction "RESET_30") (pintype "input"))
    )
    (net (code "107") (name "RI") (class "Default")
      (node (ref "U$2") (pin "11") (pinfunction "RI_11") (pintype "bidirectional"))
    )
    (net (code "108") (name "RS232") (class "Default")
      (node (ref "U$2") (pin "15") (pinfunction "RS232_15") (pintype "bidirectional"))
    )
    (net (code "109") (name "RTS") (class "Default")
      (node (ref "U$2") (pin "14") (pinfunction "RTS_14") (pintype "bidirectional"))
    )
    (net (code "110") (name "RX") (class "Default")
      (node (ref "R2") (pin "1") (pinfunction "1_1") (pintype "passive"))
      (node (ref "U$2") (pin "3") (pinfunction "RX_3") (pintype "bidirectional"))
    )
    (net (code "111") (name "RX1") (class "Default")
      (node (ref "ESP8266") (pin "RX") (pinfunction "RXD_RX") (pintype "bidirectional"))
      (node (ref "RXE") (pin "1") (pinfunction "1_1") (pintype "passive"))
    )
    (net (code "112") (name "RXC") (class "Default")
      (node (ref "PORT-E") (pin "8") (pinfunction "8_8") (pintype "passive"))
      (node (ref "TXE") (pin "2") (pinfunction "2_2") (pintype "passive"))
      (node (ref "TXJ") (pin "2") (pinfunction "2_2") (pintype "passive"))
      (node (ref "U1") (pin "2") (pinfunction "(RXD0/PCIN8)PE0_2") (pintype "bidirectional"))
    )
    (net (code "113") (name "SCK") (class "Default")
      (node (ref "PORT-B") (pin "7") (pinfunction "7_7") (pintype "passive"))
      (node (ref "SPI") (pin "7") (pinfunction "SCK_7") (pintype "passive"))
      (node (ref "U1") (pin "20") (pinfunction "(SCK/PCINT1)PB1_20") (pintype "bidirectional"))
    )
    (net (code "114") (name "TX") (class "Default")
      (node (ref "R3") (pin "1") (pinfunction "1_1") (pintype "passive"))
      (node (ref "U$2") (pin "2") (pinfunction "TX_2") (pintype "bidirectional"))
    )
    (net (code "115") (name "TX1") (class "Default")
      (node (ref "ESP8266") (pin "TX") (pinfunction "TXD_TX") (pintype "bidirectional"))
      (node (ref "TXE") (pin "1") (pinfunction "1_1") (pintype "passive"))
    )
    (net (code "116") (name "TXC") (class "Default")
      (node (ref "PORT-E") (pin "7") (pinfunction "7_7") (pintype "passive"))
      (node (ref "RXE") (pin "2") (pinfunction "2_2") (pintype "passive"))
      (node (ref "RXJ") (pin "2") (pinfunction "2_2") (pintype "passive"))
      (node (ref "U1") (pin "3") (pinfunction "(TXD0)PE1_3") (pintype "bidirectional"))
    )
    (net (code "117") (name "VCC") (class "Default")
      (node (ref "SPI") (pin "2") (pinfunction "VCC_2") (pintype "power_in"))
    )
    (net (code "118") (name "VIN") (class "Default")
      (node (ref "U4") (pin "3") (pinfunction "VIN_3") (pintype "input"))
    )
    (net (code "119") (name "XI") (class "Default")
      (node (ref "C2") (pin "2") (pinfunction "2_2") (pintype "passive"))
      (node (ref "U$2") (pin "7") (pinfunction "XI_7") (pintype "bidirectional"))
      (node (ref "Y1") (pin "2") (pinfunction "2_2") (pintype "passive"))
    )
    (net (code "120") (name "XO") (class "Default")
      (node (ref "C1") (pin "2") (pinfunction "2_2") (pintype "passive"))
      (node (ref "U$2") (pin "8") (pinfunction "XO_8") (pintype "bidirectional"))
      (node (ref "Y1") (pin "1") (pinfunction "1_1") (pintype "passive"))
    )
    (net (code "121") (name "XTAL1") (class "Default")
      (node (ref "C10") (pin "2") (pinfunction "2_2") (pintype "passive"))
      (node (ref "U1") (pin "34") (pinfunction "XTAL1_34") (pintype "input"))
      (node (ref "Y2") (pin "2") (pinfunction "2_2") (pintype "passive"))
    )
    (net (code "122") (name "XTAL2") (class "Default")
      (node (ref "C9") (pin "2") (pinfunction "2_2") (pintype "passive"))
      (node (ref "U1") (pin "33") (pinfunction "XTAL2_33") (pintype "output"))
      (node (ref "Y2") (pin "1") (pinfunction "1_1") (pintype "passive"))
    )
  )
)
